# BMS-S09-V01-TemperatureSensors.net
KiCad netlist of a schematic drawn in Altium Designer
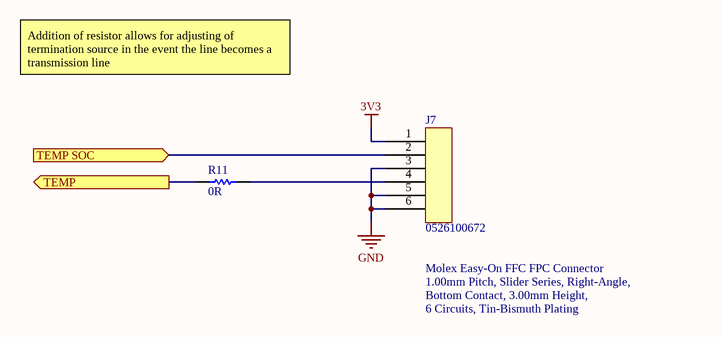
[diagram p0: BMS-S09-V01-TemperatureSensors.SchDoc]

(export (version "E")
  (design (tool "Eeschema 10.0.6"))
  (components
    (comp (ref "J7")
      (value "0526100672")
      (footprint "526100672")
      (libsource (lib "FFCConnectors") (part "6PinMOLEX"))
    )
    (comp (ref "R11")
      (value "0R")
      (footprint "Res_ThinFilm_0603")
      (description "Resistor, SMD, 0R, 0.1W, 5%, 0603")
      (libsource (lib "StandardResistors") (part "0R 5% 0603"))
    )
  )
  (nets
    (net (code "1") (name "/TEMP") (class "Default")
      (node (ref "R11") (pin "1") (pinfunction "1_1") (pintype "passive"))
    )
    (net (code "2") (name "/TEMP SOC") (class "Default")
      (node (ref "J7") (pin "2") (pinfunction "1_2") (pintype "passive"))
    )
    (net (code "3") (name "3V3") (class "Default")
      (node (ref "J7") (pin "1") (pinfunction "0_1") (pintype "passive"))
    )
    (net (code "4") (name "GND") (class "Default")
      (node (ref "J7") (pin "3") (pinfunction "2_3") (pintype "passive"))
      (node (ref "J7") (pin "5") (pinfunction "4_5") (pintype "passive"))
      (node (ref "J7") (pin "6") (pinfunction "5_6") (pintype "passive"))
    )
    (net (code "5") (name "Net-(J7-3)") (class "Default")
      (node (ref "J7") (pin "4") (pinfunction "3_4") (pintype "passive"))
      (node (ref "R11") (pin "2") (pinfunction "2_2") (pintype "passive"))
    )
  )
)
